# SW6208_A_B_C_LED__188.net
KiCad netlist of a schematic drawn in Altium Designer
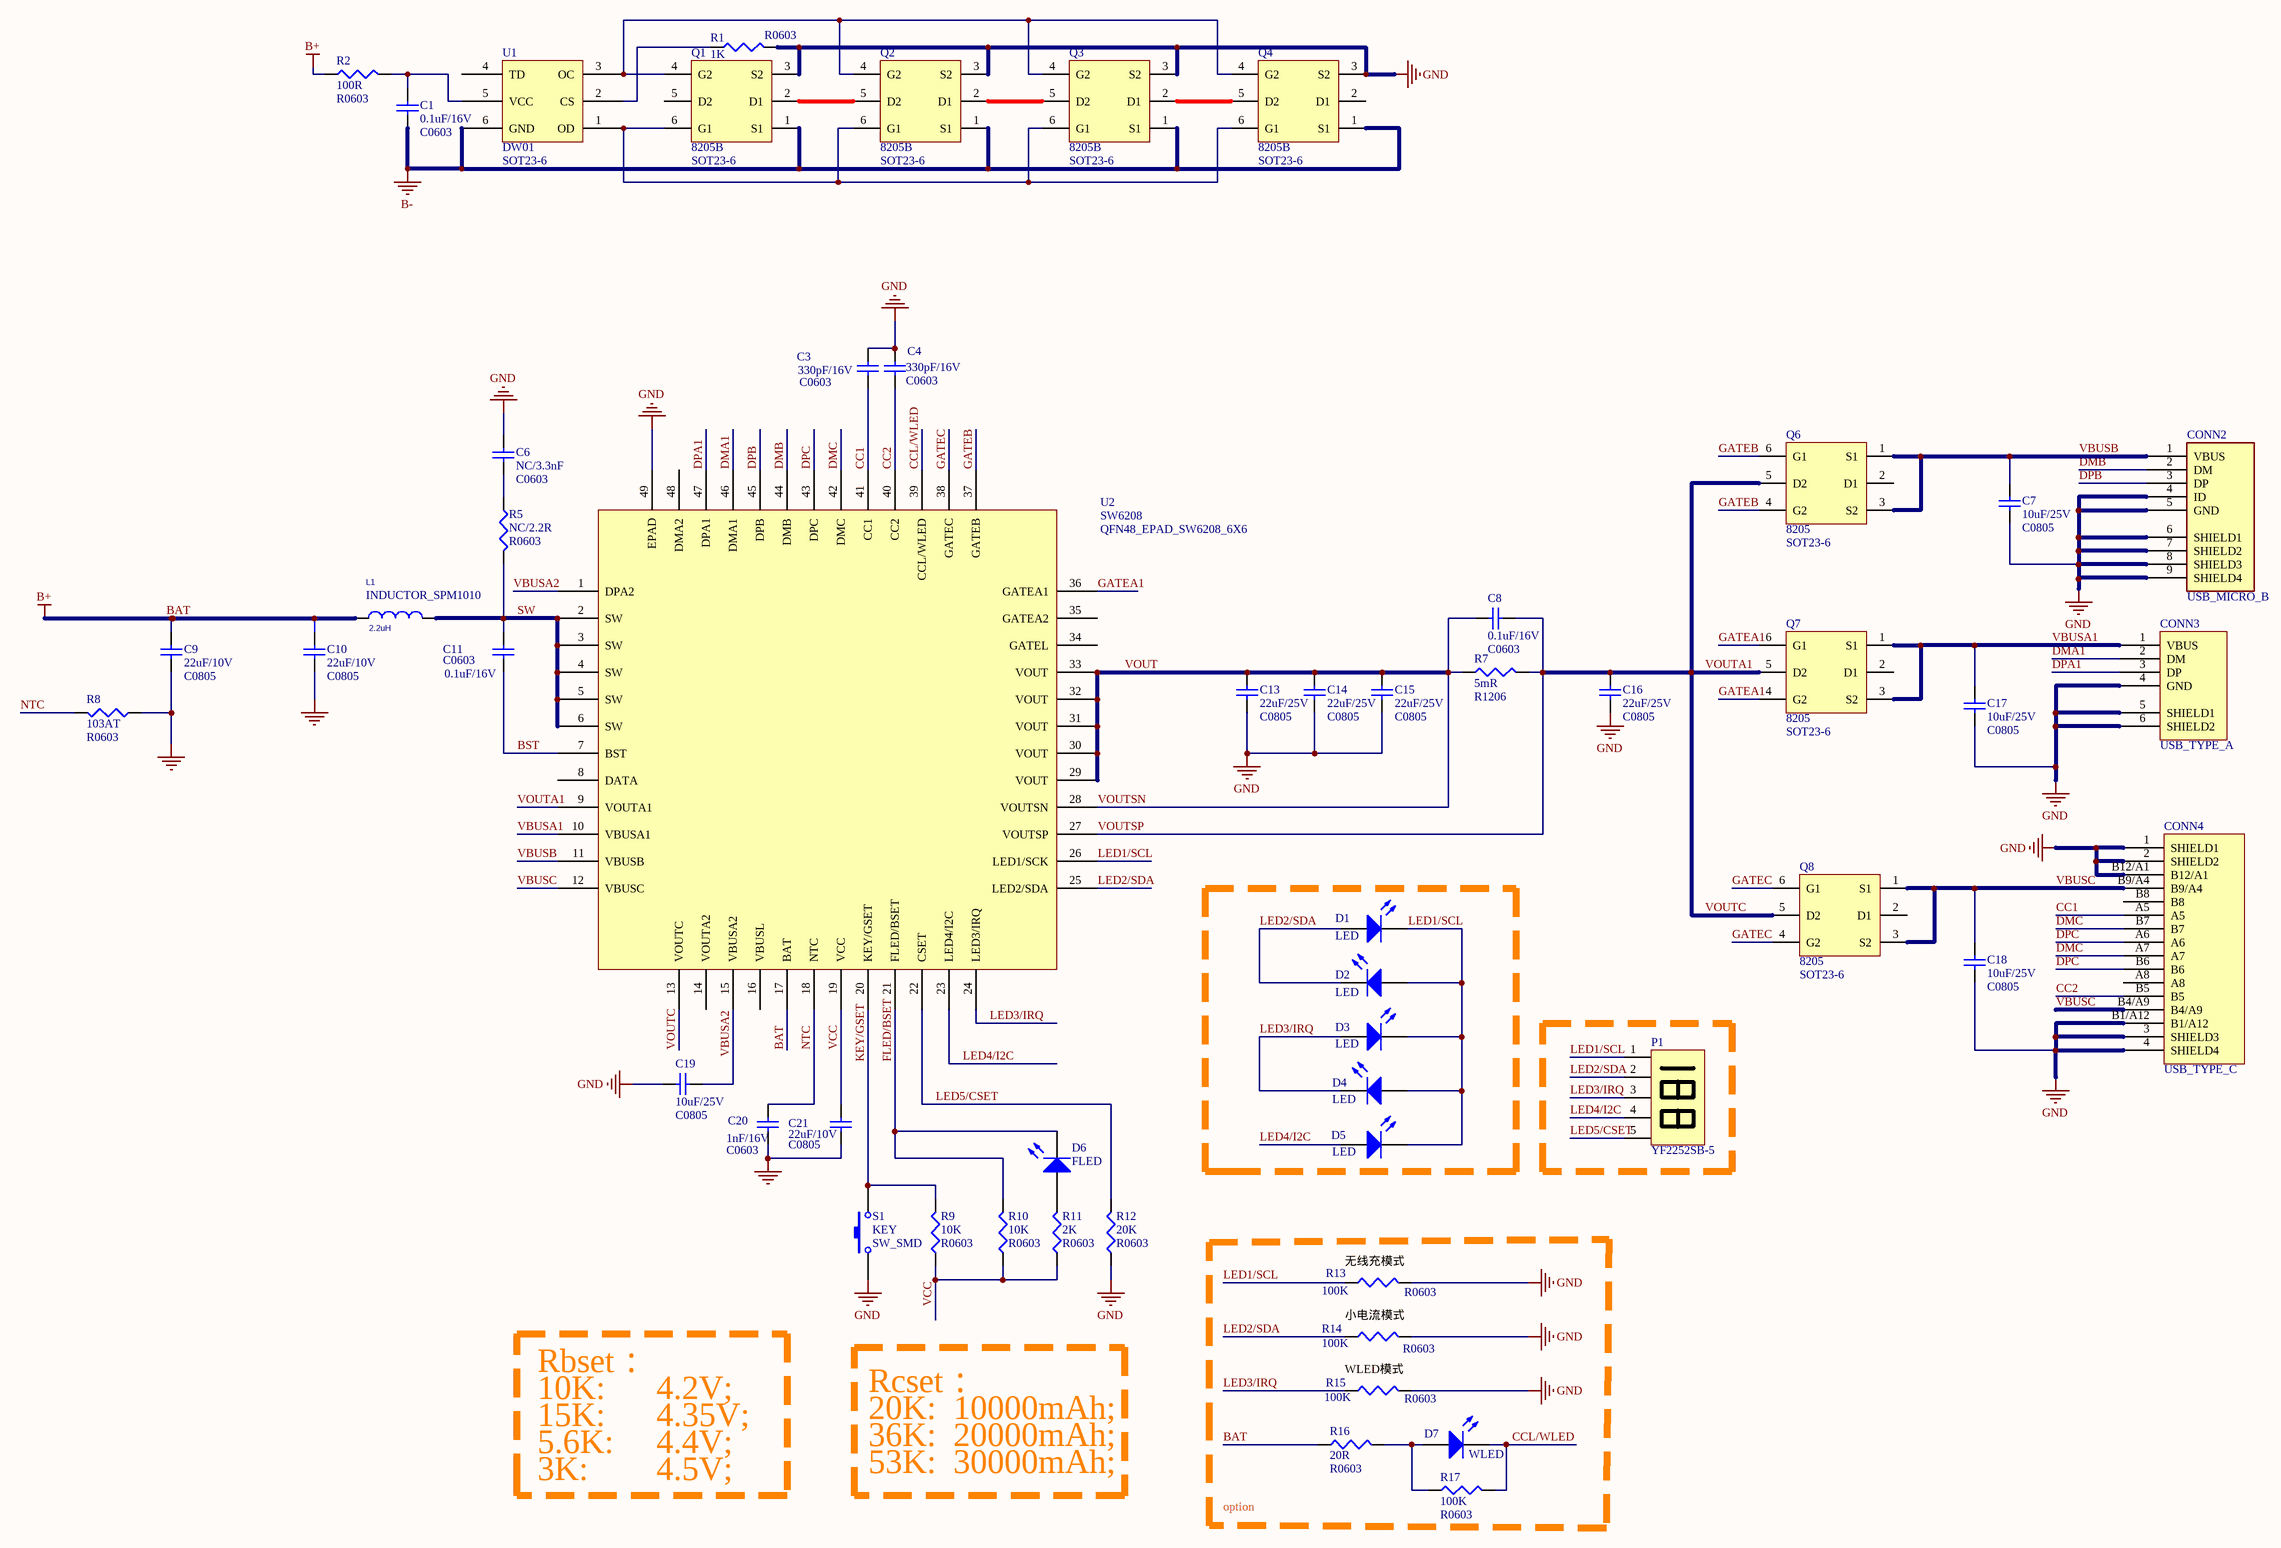
[diagram p0: SW6208+A+B+C+LED_普通188数码管.SchDoc]

(export (version "E")
  (design (tool "Eeschema 10.0.6"))
  (components
    (comp (ref "C1")
      (value "0.1uF/16V")
      (footprint "C0603")
      (description "Capacitor")
      (fields (field (name "PUBLISHER") "Altium Limited"))
      (libsource (lib "参考设计器件原理图更新") (part "CAP0603"))
    )
    (comp (ref "C3")
      (value "330pF/16V")
      (footprint "C0603")
      (description "Capacitor")
      (fields (field (name "PUBLISHER") "Altium Limited"))
      (libsource (lib "参考设计器件原理图更新") (part "CAP0603"))
    )
    (comp (ref "C4")
      (value "330pF/16V")
      (footprint "C0603")
      (description "Capacitor")
      (fields (field (name "PUBLISHER") "Altium Limited"))
      (libsource (lib "参考设计器件原理图更新") (part "CAP0603"))
    )
    (comp (ref "C6")
      (value "NC/3.3nF")
      (footprint "C0603")
      (description "Capacitor")
      (fields (field (name "PUBLISHER") "Altium Limited"))
      (libsource (lib "参考设计器件原理图更新") (part "CAP0603"))
    )
    (comp (ref "C7")
      (value "10uF/25V")
      (footprint "C0805")
      (description "Capacitor")
      (fields (field (name "PUBLISHER") "Altium Limited"))
      (libsource (lib "参考设计器件原理图更新") (part "CAP0805"))
    )
    (comp (ref "C8")
      (value "0.1uF/16V")
      (footprint "C0603")
      (description "Capacitor")
      (fields (field (name "PUBLISHER") "Altium Limited"))
      (libsource (lib "参考设计器件原理图更新") (part "CAP0603"))
    )
    (comp (ref "C9")
      (value "22uF/10V")
      (footprint "C0805")
      (description "Capacitor")
      (fields (field (name "PUBLISHER") "Altium Limited"))
      (libsource (lib "参考设计器件原理图更新") (part "CAP0805"))
    )
    (comp (ref "C10")
      (value "22uF/10V")
      (footprint "C0805")
      (description "Capacitor")
      (fields (field (name "PUBLISHER") "Altium Limited"))
      (libsource (lib "参考设计器件原理图更新") (part "CAP0805"))
    )
    (comp (ref "C11")
      (value "0.1uF/16V")
      (footprint "C0603")
      (description "Capacitor")
      (fields (field (name "PUBLISHER") "Altium Limited"))
      (libsource (lib "参考设计器件原理图更新") (part "CAP0603"))
    )
    (comp (ref "C13")
      (value "22uF/25V")
      (footprint "C0805")
      (description "Capacitor")
      (fields (field (name "PUBLISHER") "Altium Limited"))
      (libsource (lib "参考设计器件原理图更新") (part "CAP0805"))
    )
    (comp (ref "C14")
      (value "22uF/25V")
      (footprint "C0805")
      (description "Capacitor")
      (fields (field (name "PUBLISHER") "Altium Limited"))
      (libsource (lib "参考设计器件原理图更新") (part "CAP0805"))
    )
    (comp (ref "C15")
      (value "22uF/25V")
      (footprint "C0805")
      (description "Capacitor")
      (fields (field (name "PUBLISHER") "Altium Limited"))
      (libsource (lib "参考设计器件原理图更新") (part "CAP0805"))
    )
    (comp (ref "C16")
      (value "22uF/25V")
      (footprint "C0805")
      (description "Capacitor")
      (fields (field (name "PUBLISHER") "Altium Limited"))
      (libsource (lib "参考设计器件原理图更新") (part "CAP0805"))
    )
    (comp (ref "C17")
      (value "10uF/25V")
      (footprint "C0805")
      (description "Capacitor")
      (fields (field (name "PUBLISHER") "Altium Limited"))
      (libsource (lib "参考设计器件原理图更新") (part "CAP0805"))
    )
    (comp (ref "C18")
      (value "10uF/25V")
      (footprint "C0805")
      (description "Capacitor")
      (fields (field (name "PUBLISHER") "Altium Limited"))
      (libsource (lib "参考设计器件原理图更新") (part "CAP0805"))
    )
    (comp (ref "C19")
      (value "10uF/25V")
      (footprint "C0805")
      (description "Capacitor")
      (fields (field (name "PUBLISHER") "Altium Limited"))
      (libsource (lib "参考设计器件原理图更新") (part "CAP0805"))
    )
    (comp (ref "C20")
      (value "1nF/16V")
      (footprint "C0603")
      (description "Capacitor")
      (fields (field (name "PUBLISHER") "Altium Limited"))
      (libsource (lib "参考设计器件原理图更新") (part "CAP0603"))
    )
    (comp (ref "C21")
      (value "22uF/10V")
      (footprint "C0805")
      (description "Capacitor")
      (fields (field (name "PUBLISHER") "Altium Limited"))
      (libsource (lib "参考设计器件原理图更新") (part "CAP0805"))
    )
    (comp (ref "CONN2")
      (value "USB_MICRO_B")
      (footprint "USB_MICRO_B")
      (libsource (lib "参考设计器件原理图更新") (part "USB_MICRO_B"))
    )
    (comp (ref "CONN3")
      (value "USB_TYPE_A")
      (footprint "USB_TYPE_A")
      (libsource (lib "参考设计器件原理图更新") (part "USB_TYPE_A"))
    )
    (comp (ref "CONN4")
      (value "USB_TYPE_C")
      (footprint "LOUISAD:USB_TYPE_C")
      (libsource (lib "参考设计器件原理图更新") (part "USB_TYPE_C"))
    )
    (comp (ref "D1")
      (value "LED")
      (footprint "LED0603")
      (fields (field (name "PUBLISHER") "Altium Limited"))
      (libsource (lib "参考设计器件原理图更新") (part "LED_0603"))
    )
    (comp (ref "D2")
      (value "LED")
      (footprint "LED0603")
      (fields (field (name "PUBLISHER") "Altium Limited"))
      (libsource (lib "参考设计器件原理图更新") (part "LED_0603"))
    )
    (comp (ref "D3")
      (value "LED")
      (footprint "LED0603")
      (fields (field (name "PUBLISHER") "Altium Limited"))
      (libsource (lib "参考设计器件原理图更新") (part "LED_0603"))
    )
    (comp (ref "D4")
      (value "LED")
      (footprint "LED0603")
      (fields (field (name "PUBLISHER") "Altium Limited"))
      (libsource (lib "参考设计器件原理图更新") (part "LED_0603"))
    )
    (comp (ref "D5")
      (value "LED")
      (footprint "LED0603")
      (fields (field (name "PUBLISHER") "Altium Limited"))
      (libsource (lib "参考设计器件原理图更新") (part "LED_0603"))
    )
    (comp (ref "D6")
      (value "FLED")
      (footprint "LED0603")
      (description "LED")
      (fields (field (name "PUBLISHER") "Altium Limited"))
      (libsource (lib "参考设计器件原理图更新") (part "LED_0603"))
    )
    (comp (ref "D7")
      (value "WLED")
      (footprint "LED_5MM")
      (fields (field (name "PUBLISHER") "Altium Limited"))
      (libsource (lib "参考设计器件原理图更新") (part "WLED"))
    )
    (comp (ref "L1")
      (value "2.2uH")
      (footprint "INDUCTOR_SPM1010")
      (description "INDUCTOR")
      (libsource (lib "参考设计器件原理图更新") (part "INDUCTOR_SPM1010"))
    )
    (comp (ref "P1")
      (value "YF2252SB-5")
      (footprint "LED_Display_5")
      (description "188_LED_Display")
      (libsource (lib "参考设计器件原理图更新") (part "LED_Display_5"))
    )
    (comp (ref "Q1")
      (value "8205B")
      (footprint "SOT23-6")
      (description "NMOS")
      (fields (field (name "FOOTPRINF") "SOT23-6"))
      (libsource (lib "") (part "8205_1"))
    )
    (comp (ref "Q2")
      (value "8205B")
      (footprint "SOT23-6")
      (description "NMOS")
      (fields (field (name "FOOTPRINF") "SOT23-6"))
      (libsource (lib "") (part "8205_1"))
    )
    (comp (ref "Q3")
      (value "8205B")
      (footprint "SOT23-6")
      (description "NMOS")
      (fields (field (name "FOOTPRINF") "SOT23-6"))
      (libsource (lib "") (part "8205_1"))
    )
    (comp (ref "Q4")
      (value "8205B")
      (footprint "SOT23-6")
      (description "NMOS")
      (fields (field (name "FOOTPRINF") "SOT23-6"))
      (libsource (lib "") (part "8205_1"))
    )
    (comp (ref "Q6")
      (value "8205")
      (footprint "SOT23-6")
      (description "NMOS")
      (fields (field (name "FOOTPRINF") "SOT23-6"))
      (libsource (lib "参考设计器件原理图更新") (part "8205"))
    )
    (comp (ref "Q7")
      (value "8205")
      (footprint "SOT23-6")
      (description "NMOS")
      (fields (field (name "FOOTPRINF") "SOT23-6"))
      (libsource (lib "参考设计器件原理图更新") (part "8205"))
    )
    (comp (ref "Q8")
      (value "8205")
      (footprint "SOT23-6")
      (description "NMOS")
      (fields (field (name "FOOTPRINF") "SOT23-6"))
      (libsource (lib "参考设计器件原理图更新") (part "8205"))
    )
    (comp (ref "R1")
      (value "1K")
      (footprint "R0603")
      (description "Resistor")
      (fields (field (name "PUBLISHER") "Altium Limited"))
      (libsource (lib "参考设计器件原理图更新") (part "RES_0603"))
    )
    (comp (ref "R2")
      (value "100R")
      (footprint "R0603")
      (description "Resistor")
      (fields (field (name "PUBLISHER") "Altium Limited"))
      (libsource (lib "参考设计器件原理图更新") (part "RES_0603"))
    )
    (comp (ref "R5")
      (value "NC/2.2R")
      (footprint "R0603")
      (description "Resistor")
      (fields (field (name "PUBLISHER") "Altium Limited"))
      (libsource (lib "参考设计器件原理图更新") (part "RES_0603"))
    )
    (comp (ref "R7")
      (value "5mR")
      (footprint "R1206")
      (description "Resistor")
      (fields (field (name "PUBLISHER") "Altium Limited"))
      (libsource (lib "参考设计器件原理图更新") (part "RES_1206"))
    )
    (comp (ref "R8")
      (value "103AT")
      (footprint "R0603")
      (description "Resistor")
      (fields (field (name "PUBLISHER") "Altium Limited"))
      (libsource (lib "参考设计器件原理图更新") (part "RES_0603"))
    )
    (comp (ref "R9")
      (value "10K")
      (footprint "R0603")
      (description "Resistor")
      (fields (field (name "PUBLISHER") "Altium Limited"))
      (libsource (lib "参考设计器件原理图更新") (part "RES_0603"))
    )
    (comp (ref "R10")
      (value "10K")
      (footprint "R0603")
      (description "Resistor")
      (fields (field (name "PUBLISHER") "Altium Limited"))
      (libsource (lib "参考设计器件原理图更新") (part "RES_0603"))
    )
    (comp (ref "R11")
      (value "2K")
      (footprint "R0603")
      (description "Resistor")
      (fields (field (name "PUBLISHER") "Altium Limited"))
      (libsource (lib "参考设计器件原理图更新") (part "RES_0603"))
    )
    (comp (ref "R12")
      (value "20K")
      (footprint "R0603")
      (description "Resistor")
      (fields (field (name "PUBLISHER") "Altium Limited"))
      (libsource (lib "参考设计器件原理图更新") (part "RES_0603"))
    )
    (comp (ref "R13")
      (value "100K")
      (footprint "R0603")
      (description "Resistor")
      (fields (field (name "PUBLISHER") "Altium Limited"))
      (libsource (lib "参考设计器件原理图更新") (part "RES_0603"))
    )
    (comp (ref "R14")
      (value "100K")
      (footprint "R0603")
      (description "Resistor")
      (fields (field (name "PUBLISHER") "Altium Limited"))
      (libsource (lib "参考设计器件原理图更新") (part "RES_0603"))
    )
    (comp (ref "R15")
      (value "100K")
      (footprint "R0603")
      (description "Resistor")
      (fields (field (name "PUBLISHER") "Altium Limited"))
      (libsource (lib "参考设计器件原理图更新") (part "RES_0603"))
    )
    (comp (ref "R16")
      (value "20R")
      (footprint "R0603")
      (description "Resistor")
      (fields (field (name "PUBLISHER") "Altium Limited"))
      (libsource (lib "参考设计器件原理图更新") (part "RES_0603"))
    )
    (comp (ref "R17")
      (value "100K")
      (footprint "R0603")
      (description "Resistor")
      (fields (field (name "PUBLISHER") "Altium Limited"))
      (libsource (lib "参考设计器件原理图更新") (part "RES_0603"))
    )
    (comp (ref "S1")
      (value "KEY")
      (footprint "SW_SMD")
      (fields (field (name "FOOTPRINF") "SW_SMD"))
      (libsource (lib "参考设计器件原理图更新") (part "SW K"))
    )
    (comp (ref "U1")
      (value "DW01")
      (footprint "SOT23-6")
      (description "BAT_PROTECT_IC")
      (libsource (lib "参考设计器件原理图更新") (part "DW01"))
    )
    (comp (ref "U2")
      (value "SW6208")
      (footprint "QFN48_EPAD_SW6208_6X6")
      (description "IC")
      (libsource (lib "芯片型号原理图") (part "SW6208"))
    )
  )
  (nets
    (net (code "1") (name "/BST") (class "Default")
      (node (ref "C11") (pin "1") (pinfunction "1_1") (pintype "passive"))
      (node (ref "U2") (pin "7") (pinfunction "BST_7") (pintype "passive"))
    )
    (net (code "2") (name "/CC1") (class "Default")
      (node (ref "C3") (pin "1") (pinfunction "1_1") (pintype "passive"))
      (node (ref "CONN4") (pin "A5") (pinfunction "A5_A5") (pintype "passive"))
      (node (ref "U2") (pin "41") (pinfunction "CC1_41") (pintype "passive"))
    )
    (net (code "3") (name "/CC2") (class "Default")
      (node (ref "C4") (pin "1") (pinfunction "1_1") (pintype "passive"))
      (node (ref "CONN4") (pin "B5") (pinfunction "B5_B5") (pintype "passive"))
      (node (ref "U2") (pin "40") (pinfunction "CC2_40") (pintype "passive"))
    )
    (net (code "4") (name "/CCL{slash}WLED") (class "Default")
      (node (ref "D7") (pin "2") (pinfunction "K_2") (pintype "passive"))
      (node (ref "R17") (pin "2") (pinfunction "2_2") (pintype "passive"))
      (node (ref "U2") (pin "39") (pinfunction "CCL/WLED_39") (pintype "passive"))
    )
    (net (code "5") (name "/DMA1") (class "Default")
      (node (ref "CONN3") (pin "2") (pinfunction "DM_2") (pintype "passive"))
      (node (ref "U2") (pin "46") (pinfunction "DMA1_46") (pintype "passive"))
    )
    (net (code "6") (name "/DMB") (class "Default")
      (node (ref "CONN2") (pin "2") (pinfunction "DM_2") (pintype "passive"))
      (node (ref "U2") (pin "44") (pinfunction "DMB_44") (pintype "passive"))
    )
    (net (code "7") (name "/DMC") (class "Default")
      (node (ref "CONN4") (pin "A7") (pinfunction "A7_A7") (pintype "passive"))
      (node (ref "CONN4") (pin "B7") (pinfunction "B7_B7") (pintype "passive"))
      (node (ref "U2") (pin "42") (pinfunction "DMC_42") (pintype "passive"))
    )
    (net (code "8") (name "/DPA1") (class "Default")
      (node (ref "CONN3") (pin "3") (pinfunction "DP_3") (pintype "passive"))
      (node (ref "U2") (pin "47") (pinfunction "DPA1_47") (pintype "passive"))
    )
    (net (code "9") (name "/DPB") (class "Default")
      (node (ref "CONN2") (pin "3") (pinfunction "DP_3") (pintype "passive"))
      (node (ref "U2") (pin "45") (pinfunction "DPB_45") (pintype "passive"))
    )
    (net (code "10") (name "/DPC") (class "Default")
      (node (ref "CONN4") (pin "A6") (pinfunction "A6_A6") (pintype "passive"))
      (node (ref "CONN4") (pin "B6") (pinfunction "B6_B6") (pintype "passive"))
      (node (ref "U2") (pin "43") (pinfunction "DPC_43") (pintype "passive"))
    )
    (net (code "11") (name "/FLED{slash}BSET") (class "Default")
      (node (ref "D6") (pin "2") (pinfunction "K_2") (pintype "passive"))
      (node (ref "R10") (pin "2") (pinfunction "2_2") (pintype "passive"))
      (node (ref "U2") (pin "21") (pinfunction "FLED/BSET_21") (pintype "passive"))
    )
    (net (code "12") (name "/GATEA1") (class "Default")
      (node (ref "Q7") (pin "4") (pinfunction "G2_4") (pintype "passive"))
      (node (ref "Q7") (pin "6") (pinfunction "G1_6") (pintype "passive"))
      (node (ref "U2") (pin "36") (pinfunction "GATEA1_36") (pintype "passive"))
    )
    (net (code "13") (name "/GATEB") (class "Default")
      (node (ref "Q6") (pin "4") (pinfunction "G2_4") (pintype "passive"))
      (node (ref "Q6") (pin "6") (pinfunction "G1_6") (pintype "passive"))
      (node (ref "U2") (pin "37") (pinfunction "GATEB_37") (pintype "passive"))
    )
    (net (code "14") (name "/GATEC") (class "Default")
      (node (ref "Q8") (pin "4") (pinfunction "G2_4") (pintype "passive"))
      (node (ref "Q8") (pin "6") (pinfunction "G1_6") (pintype "passive"))
      (node (ref "U2") (pin "38") (pinfunction "GATEC_38") (pintype "passive"))
    )
    (net (code "15") (name "/KEY{slash}GSET") (class "Default")
      (node (ref "R9") (pin "2") (pinfunction "2_2") (pintype "passive"))
      (node (ref "S1") (pin "2") (pinfunction "2_2") (pintype "passive"))
      (node (ref "U2") (pin "20") (pinfunction "KEY/GSET_20") (pintype "passive"))
    )
    (net (code "16") (name "/LED1{slash}SCL") (class "Default")
      (node (ref "D1") (pin "2") (pinfunction "K_2") (pintype "passive"))
      (node (ref "D2") (pin "1") (pinfunction "A_1") (pintype "passive"))
      (node (ref "D3") (pin "2") (pinfunction "K_2") (pintype "passive"))
      (node (ref "D4") (pin "1") (pinfunction "A_1") (pintype "passive"))
      (node (ref "D5") (pin "2") (pinfunction "K_2") (pintype "passive"))
      (node (ref "P1") (pin "1") (pinfunction "F_1") (pintype "passive"))
      (node (ref "R13") (pin "1") (pinfunction "1_1") (pintype "passive"))
      (node (ref "U2") (pin "26") (pinfunction "LED1/SCK_26") (pintype "passive"))
    )
    (net (code "17") (name "/LED2{slash}SDA") (class "Default")
      (node (ref "D1") (pin "1") (pinfunction "A_1") (pintype "passive"))
      (node (ref "D2") (pin "2") (pinfunction "K_2") (pintype "passive"))
      (node (ref "P1") (pin "2") (pinfunction "C_2") (pintype "passive"))
      (node (ref "R14") (pin "1") (pinfunction "1_1") (pintype "passive"))
      (node (ref "U2") (pin "25") (pinfunction "LED2/SDA_25") (pintype "passive"))
    )
    (net (code "18") (name "/LED3{slash}IRQ") (class "Default")
      (node (ref "D3") (pin "1") (pinfunction "A_1") (pintype "passive"))
      (node (ref "D4") (pin "2") (pinfunction "K_2") (pintype "passive"))
      (node (ref "P1") (pin "3") (pinfunction "D_3") (pintype "passive"))
      (node (ref "R15") (pin "1") (pinfunction "1_1") (pintype "passive"))
      (node (ref "U2") (pin "24") (pinfunction "LED3/IRQ_24") (pintype "passive"))
    )
    (net (code "19") (name "/LED4{slash}I2C") (class "Default")
      (node (ref "D5") (pin "1") (pinfunction "A_1") (pintype "passive"))
      (node (ref "P1") (pin "4") (pinfunction "E_4") (pintype "passive"))
      (node (ref "U2") (pin "23") (pinfunction "LED4/I2C_23") (pintype "passive"))
    )
    (net (code "20") (name "/LED5{slash}CSET") (class "Default")
      (node (ref "P1") (pin "5") (pinfunction "G_5") (pintype "passive"))
      (node (ref "R12") (pin "2") (pinfunction "2_2") (pintype "passive"))
      (node (ref "U2") (pin "22") (pinfunction "CSET_22") (pintype "passive"))
    )
    (net (code "21") (name "/NTC") (class "Default")
      (node (ref "C20") (pin "1") (pinfunction "1_1") (pintype "passive"))
      (node (ref "R8") (pin "2") (pinfunction "2_2") (pintype "passive"))
      (node (ref "U2") (pin "18") (pinfunction "NTC_18") (pintype "passive"))
    )
    (net (code "22") (name "/SW") (class "Default")
      (node (ref "C11") (pin "2") (pinfunction "2_2") (pintype "passive"))
      (node (ref "L1") (pin "2") (pinfunction "2_2") (pintype "passive"))
      (node (ref "R5") (pin "2") (pinfunction "2_2") (pintype "passive"))
      (node (ref "U2") (pin "2") (pinfunction "SW_2") (pintype "passive"))
      (node (ref "U2") (pin "3") (pinfunction "SW_3") (pintype "passive"))
      (node (ref "U2") (pin "4") (pinfunction "SW_4") (pintype "passive"))
      (node (ref "U2") (pin "5") (pinfunction "SW_5") (pintype "passive"))
      (node (ref "U2") (pin "6") (pinfunction "SW_6") (pintype "passive"))
    )
    (net (code "23") (name "/VBUSA1") (class "Default")
      (node (ref "C17") (pin "2") (pinfunction "2_2") (pintype "passive"))
      (node (ref "CONN3") (pin "1") (pinfunction "VBUS_1") (pintype "passive"))
      (node (ref "Q7") (pin "1") (pinfunction "S1_1") (pintype "passive"))
      (node (ref "Q7") (pin "3") (pinfunction "S2_3") (pintype "passive"))
      (node (ref "U2") (pin "10") (pinfunction "VBUSA1_10") (pintype "passive"))
    )
    (net (code "24") (name "/VBUSA2") (class "Default")
      (node (ref "C19") (pin "2") (pinfunction "2_2") (pintype "passive"))
      (node (ref "U2") (pin "1") (pinfunction "DPA2_1") (pintype "passive"))
      (node (ref "U2") (pin "15") (pinfunction "VBUSA2_15") (pintype "passive"))
    )
    (net (code "25") (name "/VBUSB") (class "Default")
      (node (ref "C7") (pin "2") (pinfunction "2_2") (pintype "passive"))
      (node (ref "CONN2") (pin "1") (pinfunction "VBUS_1") (pintype "passive"))
      (node (ref "Q6") (pin "1") (pinfunction "S1_1") (pintype "passive"))
      (node (ref "Q6") (pin "3") (pinfunction "S2_3") (pintype "passive"))
      (node (ref "U2") (pin "11") (pinfunction "VBUSB_11") (pintype "passive"))
    )
    (net (code "26") (name "/VBUSC") (class "Default")
      (node (ref "C18") (pin "2") (pinfunction "2_2") (pintype "passive"))
      (node (ref "CONN4") (pin "B4/A9") (pinfunction "B4/A9_B4/A9") (pintype "passive"))
      (node (ref "CONN4") (pin "B9/A4") (pinfunction "B9/A4_B9/A4") (pintype "passive"))
      (node (ref "Q8") (pin "1") (pinfunction "S1_1") (pintype "passive"))
      (node (ref "Q8") (pin "3") (pinfunction "S2_3") (pintype "passive"))
      (node (ref "U2") (pin "12") (pinfunction "VBUSC_12") (pintype "passive"))
    )
    (net (code "27") (name "/VCC") (class "Default")
      (node (ref "C21") (pin "1") (pinfunction "1_1") (pintype "passive"))
      (node (ref "R10") (pin "1") (pinfunction "1_1") (pintype "passive"))
      (node (ref "R11") (pin "1") (pinfunction "1_1") (pintype "passive"))
      (node (ref "R9") (pin "1") (pinfunction "1_1") (pintype "passive"))
      (node (ref "U2") (pin "19") (pinfunction "VCC_19") (pintype "passive"))
    )
    (net (code "28") (name "/VOUT") (class "Default")
      (node (ref "C13") (pin "2") (pinfunction "2_2") (pintype "passive"))
      (node (ref "C14") (pin "2") (pinfunction "2_2") (pintype "passive"))
      (node (ref "C15") (pin "2") (pinfunction "2_2") (pintype "passive"))
      (node (ref "C8") (pin "1") (pinfunction "1_1") (pintype "passive"))
      (node (ref "R7") (pin "1") (pinfunction "1_1") (pintype "passive"))
      (node (ref "U2") (pin "28") (pinfunction "VOUTSN_28") (pintype "passive"))
      (node (ref "U2") (pin "29") (pinfunction "VOUT_29") (pintype "passive"))
      (node (ref "U2") (pin "30") (pinfunction "VOUT_30") (pintype "passive"))
      (node (ref "U2") (pin "31") (pinfunction "VOUT_31") (pintype "passive"))
      (node (ref "U2") (pin "32") (pinfunction "VOUT_32") (pintype "passive"))
      (node (ref "U2") (pin "33") (pinfunction "VOUT_33") (pintype "passive"))
    )
    (net (code "29") (name "/VOUTA1") (class "Default")
      (node (ref "C16") (pin "2") (pinfunction "2_2") (pintype "passive"))
      (node (ref "C8") (pin "2") (pinfunction "2_2") (pintype "passive"))
      (node (ref "Q6") (pin "5") (pinfunction "D2_5") (pintype "passive"))
      (node (ref "Q7") (pin "5") (pinfunction "D2_5") (pintype "passive"))
      (node (ref "Q8") (pin "5") (pinfunction "D2_5") (pintype "passive"))
      (node (ref "R7") (pin "2") (pinfunction "2_2") (pintype "passive"))
      (node (ref "U2") (pin "13") (pinfunction "VOUTC_13") (pintype "passive"))
      (node (ref "U2") (pin "27") (pinfunction "VOUTSP_27") (pintype "passive"))
      (node (ref "U2") (pin "9") (pinfunction "VOUTA1_9") (pintype "passive"))
    )
    (net (code "30") (name "B+") (class "Default")
      (node (ref "C10") (pin "2") (pinfunction "2_2") (pintype "passive"))
      (node (ref "C9") (pin "2") (pinfunction "2_2") (pintype "passive"))
      (node (ref "L1") (pin "1") (pinfunction "1_1") (pintype "passive"))
      (node (ref "R16") (pin "1") (pinfunction "1_1") (pintype "passive"))
      (node (ref "R2") (pin "1") (pinfunction "1_1") (pintype "passive"))
      (node (ref "U2") (pin "17") (pinfunction "BAT_17") (pintype "passive"))
    )
    (net (code "31") (name "B-") (class "Default")
      (node (ref "C1") (pin "1") (pinfunction "1_1") (pintype "passive"))
      (node (ref "Q1") (pin "1") (pinfunction "S1_1") (pintype "passive"))
      (node (ref "Q2") (pin "1") (pinfunction "S1_1") (pintype "passive"))
      (node (ref "Q3") (pin "1") (pinfunction "S1_1") (pintype "passive"))
      (node (ref "Q4") (pin "1") (pinfunction "S1_1") (pintype "passive"))
      (node (ref "U1") (pin "6") (pinfunction "GND_6") (pintype "passive"))
    )
    (net (code "32") (name "GND") (class "Default")
      (node (ref "C10") (pin "1") (pinfunction "1_1") (pintype "passive"))
      (node (ref "C13") (pin "1") (pinfunction "1_1") (pintype "passive"))
      (node (ref "C14") (pin "1") (pinfunction "1_1") (pintype "passive"))
      (node (ref "C15") (pin "1") (pinfunction "1_1") (pintype "passive"))
      (node (ref "C16") (pin "1") (pinfunction "1_1") (pintype "passive"))
      (node (ref "C17") (pin "1") (pinfunction "1_1") (pintype "passive"))
      (node (ref "C18") (pin "1") (pinfunction "1_1") (pintype "passive"))
      (node (ref "C19") (pin "1") (pinfunction "1_1") (pintype "passive"))
      (node (ref "C20") (pin "2") (pinfunction "2_2") (pintype "passive"))
      (node (ref "C21") (pin "2") (pinfunction "2_2") (pintype "passive"))
      (node (ref "C3") (pin "2") (pinfunction "2_2") (pintype "passive"))
      (node (ref "C4") (pin "2") (pinfunction "2_2") (pintype "passive"))
      (node (ref "C6") (pin "2") (pinfunction "2_2") (pintype "passive"))
      (node (ref "C7") (pin "1") (pinfunction "1_1") (pintype "passive"))
      (node (ref "C9") (pin "1") (pinfunction "1_1") (pintype "passive"))
      (node (ref "CONN2") (pin "4") (pinfunction "ID_4") (pintype "passive"))
      (node (ref "CONN2") (pin "5") (pinfunction "GND_5") (pintype "passive"))
      (node (ref "CONN2") (pin "6") (pinfunction "SHIELD1_6") (pintype "passive"))
      (node (ref "CONN2") (pin "7") (pinfunction "SHIELD2_7") (pintype "passive"))
      (node (ref "CONN2") (pin "8") (pinfunction "SHIELD3_8") (pintype "passive"))
      (node (ref "CONN2") (pin "9") (pinfunction "SHIELD4_9") (pintype "passive"))
      (node (ref "CONN3") (pin "4") (pinfunction "GND_4") (pintype "passive"))
      (node (ref "CONN3") (pin "5") (pinfunction "SHIELD1_5") (pintype "passive"))
      (node (ref "CONN3") (pin "6") (pinfunction "SHIELD2_6") (pintype "passive"))
      (node (ref "CONN4") (pin "1") (pinfunction "SHIELD1_1") (pintype "passive"))
      (node (ref "CONN4") (pin "2") (pinfunction "SHIELD2_2") (pintype "passive"))
      (node (ref "CONN4") (pin "3") (pinfunction "SHIELD3_3") (pintype "passive"))
      (node (ref "CONN4") (pin "4") (pinfunction "SHIELD4_4") (pintype "passive"))
      (node (ref "CONN4") (pin "B1/A12") (pinfunction "B1/A12_B1/A12") (pintype "passive"))
      (node (ref "CONN4") (pin "B12/A1") (pinfunction "B12/A1_B12/A1") (pintype "passive"))
      (node (ref "Q1") (pin "3") (pinfunction "S2_3") (pintype "passive"))
      (node (ref "Q2") (pin "3") (pinfunction "S2_3") (pintype "passive"))
      (node (ref "Q3") (pin "3") (pinfunction "S2_3") (pintype "passive"))
      (node (ref "Q4") (pin "3") (pinfunction "S2_3") (pintype "passive"))
      (node (ref "R1") (pin "2") (pinfunction "2_2") (pintype "passive"))
      (node (ref "R12") (pin "1") (pinfunction "1_1") (pintype "passive"))
      (node (ref "R13") (pin "2") (pinfunction "2_2") (pintype "passive"))
      (node (ref "R14") (pin "2") (pinfunction "2_2") (pintype "passive"))
      (node (ref "R15") (pin "2") (pinfunction "2_2") (pintype "passive"))
      (node (ref "R8") (pin "1") (pinfunction "1_1") (pintype "passive"))
      (node (ref "S1") (pin "1") (pinfunction "1_1") (pintype "passive"))
      (node (ref "U2") (pin "49") (pinfunction "EPAD_49") (pintype "passive"))
    )
    (net (code "33") (name "Net-(C6-Pad1)") (class "Default")
      (node (ref "C6") (pin "1") (pinfunction "1_1") (pintype "passive"))
      (node (ref "R5") (pin "1") (pinfunction "1_1") (pintype "passive"))
    )
    (net (code "34") (name "Net-(D6-A)") (class "Default")
      (node (ref "D6") (pin "1") (pinfunction "A_1") (pintype "passive"))
      (node (ref "R11") (pin "2") (pinfunction "2_2") (pintype "passive"))
    )
    (net (code "35") (name "Net-(D7-A)") (class "Default")
      (node (ref "D7") (pin "1") (pinfunction "A_1") (pintype "passive"))
      (node (ref "R16") (pin "2") (pinfunction "2_2") (pintype "passive"))
      (node (ref "R17") (pin "1") (pinfunction "1_1") (pintype "passive"))
    )
    (net (code "36") (name "Net-(Q1-D1)") (class "Default")
      (node (ref "Q1") (pin "2") (pinfunction "D1_2") (pintype "passive"))
      (node (ref "Q2") (pin "5") (pinfunction "D2_5") (pintype "passive"))
    )
    (net (code "37") (name "Net-(Q1-G1)") (class "Default")
      (node (ref "Q1") (pin "6") (pinfunction "G1_6") (pintype "passive"))
      (node (ref "Q2") (pin "6") (pinfunction "G1_6") (pintype "passive"))
      (node (ref "Q3") (pin "6") (pinfunction "G1_6") (pintype "passive"))
      (node (ref "Q4") (pin "6") (pinfunction "G1_6") (pintype "passive"))
      (node (ref "U1") (pin "1") (pinfunction "OD_1") (pintype "passive"))
    )
    (net (code "38") (name "Net-(Q1-G2)") (class "Default")
      (node (ref "Q1") (pin "4") (pinfunction "G2_4") (pintype "passive"))
      (node (ref "Q2") (pin "4") (pinfunction "G2_4") (pintype "passive"))
      (node (ref "Q3") (pin "4") (pinfunction "G2_4") (pintype "passive"))
      (node (ref "Q4") (pin "4") (pinfunction "G2_4") (pintype "passive"))
      (node (ref "U1") (pin "3") (pinfunction "OC_3") (pintype "passive"))
    )
    (net (code "39") (name "Net-(Q2-D1)") (class "Default")
      (node (ref "Q2") (pin "2") (pinfunction "D1_2") (pintype "passive"))
      (node (ref "Q3") (pin "5") (pinfunction "D2_5") (pintype "passive"))
    )
    (net (code "40") (name "Net-(Q3-D1)") (class "Default")
      (node (ref "Q3") (pin "2") (pinfunction "D1_2") (pintype "passive"))
      (node (ref "Q4") (pin "5") (pinfunction "D2_5") (pintype "passive"))
    )
    (net (code "41") (name "Net-(U1-CS)") (class "Default")
      (node (ref "R1") (pin "1") (pinfunction "1_1") (pintype "passive"))
      (node (ref "U1") (pin "2") (pinfunction "CS_2") (pintype "passive"))
    )
    (net (code "42") (name "Net-(U1-VCC)") (class "Default")
      (node (ref "C1") (pin "2") (pinfunction "2_2") (pintype "passive"))
      (node (ref "R2") (pin "2") (pinfunction "2_2") (pintype "passive"))
      (node (ref "U1") (pin "5") (pinfunction "VCC_5") (pintype "passive"))
    )
    (net (code "43") (name "unconnected-(CONN4-PadA8)") (class "Default")
      (node (ref "CONN4") (pin "A8") (pinfunction "A8_A8") (pintype "passive"))
    )
    (net (code "44") (name "unconnected-(CONN4-PadB8)") (class "Default")
      (node (ref "CONN4") (pin "B8") (pinfunction "B8_B8") (pintype "passive"))
    )
    (net (code "45") (name "unconnected-(Q1-D2-Pad5)") (class "Default")
      (node (ref "Q1") (pin "5") (pinfunction "D2_5") (pintype "passive"))
    )
    (net (code "46") (name "unconnected-(Q4-D1-Pad2)") (class "Default")
      (node (ref "Q4") (pin "2") (pinfunction "D1_2") (pintype "passive"))
    )
    (net (code "47") (name "unconnected-(Q6-D1-Pad2)") (class "Default")
      (node (ref "Q6") (pin "2") (pinfunction "D1_2") (pintype "passive"))
    )
    (net (code "48") (name "unconnected-(Q7-D1-Pad2)") (class "Default")
      (node (ref "Q7") (pin "2") (pinfunction "D1_2") (pintype "passive"))
    )
    (net (code "49") (name "unconnected-(Q8-D1-Pad2)") (class "Default")
      (node (ref "Q8") (pin "2") (pinfunction "D1_2") (pintype "passive"))
    )
    (net (code "50") (name "unconnected-(U1-TD-Pad4)") (class "Default")
      (node (ref "U1") (pin "4") (pinfunction "TD_4") (pintype "passive"))
    )
    (net (code "51") (name "unconnected-(U2-DATA-Pad8)") (class "Default")
      (node (ref "U2") (pin "8") (pinfunction "DATA_8") (pintype "passive"))
    )
    (net (code "52") (name "unconnected-(U2-DMA2-Pad48)") (class "Default")
      (node (ref "U2") (pin "48") (pinfunction "DMA2_48") (pintype "passive"))
    )
    (net (code "53") (name "unconnected-(U2-GATEA2-Pad35)") (class "Default")
      (node (ref "U2") (pin "35") (pinfunction "GATEA2_35") (pintype "passive"))
    )
    (net (code "54") (name "unconnected-(U2-GATEL-Pad34)") (class "Default")
      (node (ref "U2") (pin "34") (pinfunction "GATEL_34") (pintype "passive"))
    )
    (net (code "55") (name "unconnected-(U2-VBUSL-Pad16)") (class "Default")
      (node (ref "U2") (pin "16") (pinfunction "VBUSL_16") (pintype "passive"))
    )
    (net (code "56") (name "unconnected-(U2-VOUTA2-Pad14)") (class "Default")
      (node (ref "U2") (pin "14") (pinfunction "VOUTA2_14") (pintype "passive"))
    )
  )
)
